# LCDwen.net
KiCad netlist of a schematic drawn in Altium Designer
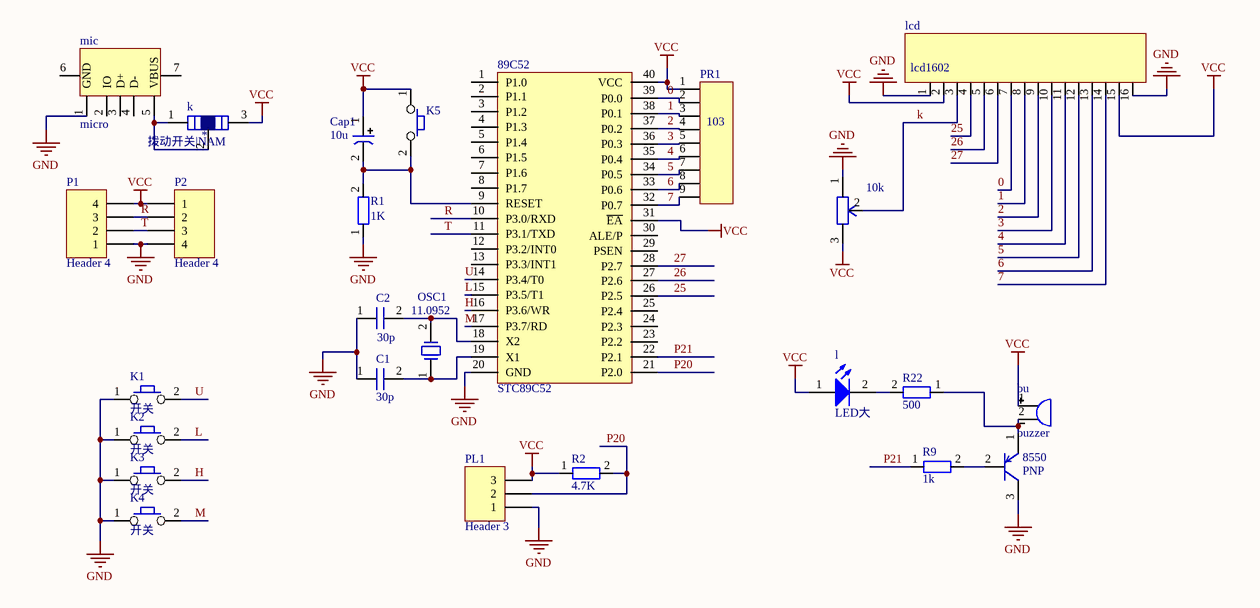
[diagram p0: LCDwen.SchDoc]

(export (version "E")
  (design (tool "Eeschema 10.0.6"))
  (components
    (comp (ref "10k") (value "~") (footprint "蓝白电位器") (libsource (lib "1412220207梁新坚元器件库") (part "蓝白电位器")))
    (comp (ref "89C52")
      (value "STC89C52")
      (footprint "AT89C52")
      (libsource (lib "1412220207梁新坚元器件库") (part "STC89C52"))
    )
    (comp (ref "8550") (value "PNP") (footprint "三极管PNP") (libsource (lib "1412220207梁新坚元器件库") (part "PNP")))
    (comp (ref "bu")
      (value "buzzer")
      (footprint "buzzer")
      (libsource (lib "1412220207梁新坚元器件库") (part "buzzer"))
    )
    (comp (ref "C1") (value "30p") (footprint "电容。") (libsource (lib "1412220207梁新坚元器件库") (part "电容")))
    (comp (ref "C2") (value "30p") (footprint "电容。") (libsource (lib "1412220207梁新坚元器件库") (part "电容")))
    (comp (ref "Cap1") (value "10u") (footprint "电容") (libsource (lib "1412220207梁新坚元器件库") (part "电解电容")))
    (comp (ref "k")
      (value "*")
      (footprint "拨动开关")
      (fields (field (name "ALTIUM_UNNAMED_1") "拨动开关"))
      (libsource (lib "1412220207梁新坚元器件库") (part "拨动开关"))
    )
    (comp (ref "K1")
      (value "~")
      (footprint "开关")
      (fields (field (name "COMMEN") "开关"))
      (libsource (lib "1412220207梁新坚元器件库") (part "开关"))
    )
    (comp (ref "K2")
      (value "~")
      (footprint "开关")
      (fields (field (name "COMMEN") "开关"))
      (libsource (lib "1412220207梁新坚元器件库") (part "开关"))
    )
    (comp (ref "K3")
      (value "~")
      (footprint "开关")
      (fields (field (name "COMMEN") "开关"))
      (libsource (lib "1412220207梁新坚元器件库") (part "开关"))
    )
    (comp (ref "K4")
      (value "~")
      (footprint "开关")
      (fields (field (name "COMMEN") "开关"))
      (libsource (lib "1412220207梁新坚元器件库") (part "开关"))
    )
    (comp (ref "K5") (value "~") (footprint "开关") (libsource (lib "1412220207梁新坚元器件库") (part "开关")))
    (comp (ref "l") (value "LED大") (footprint "LED大") (libsource (lib "1412220207梁新坚元器件库") (part "LED大")))
    (comp (ref "lcd")
      (value "lcd1602")
      (footprint "lcd1602")
      (libsource (lib "1412220207梁新坚元器件库") (part "lcd1602"))
    )
    (comp (ref "mic")
      (value "micro")
      (footprint "MICRO")
      (libsource (lib "1412220207梁新坚元器件库") (part "micro"))
    )
    (comp (ref "OSC1") (value "11.0952") (footprint "晶震") (libsource (lib "1412220207梁新坚元器件库") (part "晶震")))
    (comp (ref "P1")
      (value "Header 4")
      (footprint "HDR1X4")
      (description "Header, 4-Pin")
      (fields (field (name "PUBLISHER") "Altium Limited"))
      (libsource (lib "Miscellaneous Connectors") (part "Header 4"))
    )
    (comp (ref "P2")
      (value "Header 4")
      (footprint "HDR1X4")
      (description "Header, 4-Pin")
      (fields (field (name "PUBLISHER") "Altium Limited"))
      (libsource (lib "") (part "Header 4_1"))
    )
    (comp (ref "PL1")
      (value "Header 3")
      (footprint "HDR1X3")
      (description "Header, 3-Pin")
      (fields (field (name "PUBLISHER") "Altium Limited"))
      (libsource (lib "Miscellaneous Connectors") (part "Header 3"))
    )
    (comp (ref "PR1") (value "103") (footprint "排阻") (libsource (lib "1412220207梁新坚元器件库") (part "排阻")))
    (comp (ref "R1") (value "1K") (footprint "电阻") (libsource (lib "1412220207梁新坚元器件库") (part "电阻")))
    (comp (ref "R2") (value "4.7K") (footprint "电阻") (libsource (lib "1412220207梁新坚元器件库") (part "电阻")))
    (comp (ref "R9") (value "1k") (footprint "电阻") (libsource (lib "1412220207梁新坚元器件库") (part "电阻")))
    (comp (ref "R22") (value "500") (footprint "电阻") (libsource (lib "1412220207梁新坚元器件库") (part "电阻")))
  )
  (nets
    (net (code "1") (name "/0") (class "Default")
      (node (ref "89C52") (pin "39") (pinfunction "P0.0_39") (pintype "passive"))
      (node (ref "PR1") (pin "2") (pinfunction "2_2") (pintype "passive"))
      (node (ref "lcd") (pin "7") (pinfunction "7_7") (pintype "passive"))
    )
    (net (code "2") (name "/1") (class "Default")
      (node (ref "89C52") (pin "38") (pinfunction "P0.1_38") (pintype "passive"))
      (node (ref "PR1") (pin "3") (pinfunction "3_3") (pintype "passive"))
      (node (ref "lcd") (pin "8") (pinfunction "8_8") (pintype "passive"))
    )
    (net (code "3") (name "/2") (class "Default")
      (node (ref "89C52") (pin "37") (pinfunction "P0.2_37") (pintype "passive"))
      (node (ref "PR1") (pin "4") (pinfunction "4_4") (pintype "passive"))
      (node (ref "lcd") (pin "9") (pinfunction "9_9") (pintype "passive"))
    )
    (net (code "4") (name "/3") (class "Default")
      (node (ref "89C52") (pin "36") (pinfunction "P0.3_36") (pintype "passive"))
      (node (ref "PR1") (pin "5") (pinfunction "5_5") (pintype "passive"))
      (node (ref "lcd") (pin "10") (pinfunction "10_10") (pintype "passive"))
    )
    (net (code "5") (name "/4") (class "Default")
      (node (ref "89C52") (pin "35") (pinfunction "P0.4_35") (pintype "passive"))
      (node (ref "PR1") (pin "6") (pinfunction "6_6") (pintype "passive"))
      (node (ref "lcd") (pin "11") (pinfunction "11_11") (pintype "passive"))
    )
    (net (code "6") (name "/5") (class "Default")
      (node (ref "89C52") (pin "34") (pinfunction "P0.5_34") (pintype "passive"))
      (node (ref "PR1") (pin "7") (pinfunction "7_7") (pintype "passive"))
      (node (ref "lcd") (pin "12") (pinfunction "12_12") (pintype "passive"))
    )
    (net (code "7") (name "/6") (class "Default")
      (node (ref "89C52") (pin "33") (pinfunction "P0.6_33") (pintype "passive"))
      (node (ref "PR1") (pin "8") (pinfunction "8_8") (pintype "passive"))
      (node (ref "lcd") (pin "13") (pinfunction "13_13") (pintype "passive"))
    )
    (net (code "8") (name "/7") (class "Default")
      (node (ref "89C52") (pin "32") (pinfunction "P0.7_32") (pintype "passive"))
      (node (ref "PR1") (pin "9") (pinfunction "9_9") (pintype "passive"))
      (node (ref "lcd") (pin "14") (pinfunction "14_14") (pintype "passive"))
    )
    (net (code "9") (name "/25") (class "Default")
      (node (ref "89C52") (pin "26") (pinfunction "P2.5_26") (pintype "passive"))
      (node (ref "lcd") (pin "4") (pinfunction "4_4") (pintype "passive"))
    )
    (net (code "10") (name "/26") (class "Default")
      (node (ref "89C52") (pin "27") (pinfunction "P2.6_27") (pintype "passive"))
      (node (ref "lcd") (pin "5") (pinfunction "5_5") (pintype "passive"))
    )
    (net (code "11") (name "/27") (class "Default")
      (node (ref "89C52") (pin "28") (pinfunction "P2.7_28") (pintype "passive"))
      (node (ref "lcd") (pin "6") (pinfunction "6_6") (pintype "passive"))
    )
    (net (code "12") (name "/H") (class "Default")
      (node (ref "89C52") (pin "16") (pinfunction "P3.6/WR_16") (pintype "passive"))
      (node (ref "K3") (pin "2") (pinfunction "2_2") (pintype "passive"))
    )
    (net (code "13") (name "/L") (class "Default")
      (node (ref "89C52") (pin "15") (pinfunction "P3.5/T1_15") (pintype "passive"))
      (node (ref "K2") (pin "2") (pinfunction "2_2") (pintype "passive"))
    )
    (net (code "14") (name "/M") (class "Default")
      (node (ref "89C52") (pin "17") (pinfunction "P3.7/RD_17") (pintype "passive"))
      (node (ref "K4") (pin "2") (pinfunction "2_2") (pintype "passive"))
    )
    (net (code "15") (name "/P20") (class "Default")
      (node (ref "89C52") (pin "21") (pinfunction "P2.0_21") (pintype "passive"))
      (node (ref "PL1") (pin "2") (pinfunction "2_2") (pintype "passive"))
      (node (ref "R2") (pin "2") (pinfunction "2_2") (pintype "passive"))
    )
    (net (code "16") (name "/P21") (class "Default")
      (node (ref "89C52") (pin "22") (pinfunction "P2.1_22") (pintype "passive"))
      (node (ref "R9") (pin "1") (pinfunction "1_1") (pintype "passive"))
    )
    (net (code "17") (name "/R") (class "Default")
      (node (ref "89C52") (pin "10") (pinfunction "P3.0/RXD_10") (pintype "passive"))
      (node (ref "P1") (pin "3") (pinfunction "3_3") (pintype "passive"))
      (node (ref "P2") (pin "2") (pinfunction "2_2") (pintype "passive"))
    )
    (net (code "18") (name "/T") (class "Default")
      (node (ref "89C52") (pin "11") (pinfunction "P3.1/TXD_11") (pintype "passive"))
      (node (ref "P1") (pin "2") (pinfunction "2_2") (pintype "passive"))
      (node (ref "P2") (pin "3") (pinfunction "3_3") (pintype "passive"))
    )
    (net (code "19") (name "/U") (class "Default")
      (node (ref "89C52") (pin "14") (pinfunction "P3.4/T0_14") (pintype "passive"))
      (node (ref "K1") (pin "2") (pinfunction "2_2") (pintype "passive"))
    )
    (net (code "20") (name "/k") (class "Default")
      (node (ref "10k") (pin "2") (pinfunction "2_2") (pintype "passive"))
      (node (ref "lcd") (pin "3") (pinfunction "3_3") (pintype "passive"))
    )
    (net (code "21") (name "GND") (class "Default")
      (node (ref "10k") (pin "1") (pinfunction "1_1") (pintype "passive"))
      (node (ref "8550") (pin "3") (pinfunction "3_3") (pintype "passive"))
      (node (ref "89C52") (pin "20") (pinfunction "GND_20") (pintype "passive"))
      (node (ref "C1") (pin "1") (pinfunction "1_1") (pintype "passive"))
      (node (ref "C2") (pin "1") (pinfunction "1_1") (pintype "passive"))
      (node (ref "K1") (pin "1") (pinfunction "1_1") (pintype "passive"))
      (node (ref "K2") (pin "1") (pinfunction "1_1") (pintype "passive"))
      (node (ref "K3") (pin "1") (pinfunction "1_1") (pintype "passive"))
      (node (ref "K4") (pin "1") (pinfunction "1_1") (pintype "passive"))
      (node (ref "P1") (pin "1") (pinfunction "1_1") (pintype "passive"))
      (node (ref "P2") (pin "4") (pinfunction "4_4") (pintype "passive"))
      (node (ref "PL1") (pin "1") (pinfunction "1_1") (pintype "passive"))
      (node (ref "R1") (pin "1") (pinfunction "1_1") (pintype "passive"))
      (node (ref "lcd") (pin "1") (pinfunction "1_1") (pintype "passive"))
      (node (ref "lcd") (pin "16") (pinfunction "16_16") (pintype "passive"))
      (node (ref "mic") (pin "1") (pinfunction "GND_1") (pintype "passive"))
    )
    (net (code "22") (name "Net-(89C52-RESET)") (class "Default")
      (node (ref "89C52") (pin "9") (pinfunction "RESET_9") (pintype "passive"))
      (node (ref "Cap1") (pin "2") (pinfunction "2_2") (pintype "passive"))
      (node (ref "K5") (pin "2") (pinfunction "2_2") (pintype "passive"))
      (node (ref "R1") (pin "2") (pinfunction "2_2") (pintype "passive"))
    )
    (net (code "23") (name "Net-(89C52-X1)") (class "Default")
      (node (ref "89C52") (pin "19") (pinfunction "X1_19") (pintype "passive"))
      (node (ref "C1") (pin "2") (pinfunction "2_2") (pintype "passive"))
      (node (ref "OSC1") (pin "1") (pinfunction "1_1") (pintype "passive"))
    )
    (net (code "24") (name "Net-(89C52-X2)") (class "Default")
      (node (ref "89C52") (pin "18") (pinfunction "X2_18") (pintype "passive"))
      (node (ref "C2") (pin "2") (pinfunction "2_2") (pintype "passive"))
      (node (ref "OSC1") (pin "2") (pinfunction "2_2") (pintype "passive"))
    )
    (net (code "25") (name "Net-(8550-Pad1)") (class "Default")
      (node (ref "8550") (pin "1") (pinfunction "1_1") (pintype "passive"))
      (node (ref "R22") (pin "1") (pinfunction "1_1") (pintype "passive"))
      (node (ref "bu") (pin "2") (pinfunction "2_2") (pintype "passive"))
    )
    (net (code "26") (name "Net-(8550-Pad2)") (class "Default")
      (node (ref "8550") (pin "2") (pinfunction "2_2") (pintype "passive"))
      (node (ref "R9") (pin "2") (pinfunction "2_2") (pintype "passive"))
    )
    (net (code "27") (name "Net-(R22-Pad2)") (class "Default")
      (node (ref "R22") (pin "2") (pinfunction "2_2") (pintype "passive"))
      (node (ref "l") (pin "2") (pinfunction "2_2") (pintype "passive"))
    )
    (net (code "28") (name "Net-(mic-VBUS)") (class "Default")
      (node (ref "k") (pin "1") (pinfunction "1_1") (pintype "passive"))
      (node (ref "k") (pin "2") (pinfunction "2_2") (pintype "passive"))
      (node (ref "mic") (pin "5") (pinfunction "VBUS_5") (pintype "passive"))
    )
    (net (code "29") (name "VCC") (class "Default")
      (node (ref "10k") (pin "3") (pinfunction "3_3") (pintype "passive"))
      (node (ref "89C52") (pin "31") (pinfunction "~{EA}_31") (pintype "passive"))
      (node (ref "89C52") (pin "40") (pinfunction "VCC_40") (pintype "passive"))
      (node (ref "Cap1") (pin "1") (pinfunction "1_1") (pintype "passive"))
      (node (ref "K5") (pin "1") (pinfunction "1_1") (pintype "passive"))
      (node (ref "P1") (pin "4") (pinfunction "4_4") (pintype "passive"))
      (node (ref "P2") (pin "1") (pinfunction "1_1") (pintype "passive"))
      (node (ref "PL1") (pin "3") (pinfunction "3_3") (pintype "passive"))
      (node (ref "PR1") (pin "1") (pinfunction "1_1") (pintype "passive"))
      (node (ref "R2") (pin "1") (pinfunction "1_1") (pintype "passive"))
      (node (ref "bu") (pin "1") (pinfunction "1_1") (pintype "passive"))
      (node (ref "k") (pin "3") (pinfunction "3_3") (pintype "passive"))
      (node (ref "l") (pin "1") (pinfunction "1_1") (pintype "passive"))
      (node (ref "lcd") (pin "15") (pinfunction "15_15") (pintype "passive"))
      (node (ref "lcd") (pin "2") (pinfunction "2_2") (pintype "passive"))
    )
    (net (code "30") (name "unconnected-(89C52-ALE{slash}P-Pad30)") (class "Default")
      (node (ref "89C52") (pin "30") (pinfunction "ALE/P_30") (pintype "passive"))
    )
    (net (code "31") (name "unconnected-(89C52-P1.0-Pad1)") (class "Default")
      (node (ref "89C52") (pin "1") (pinfunction "P1.0_1") (pintype "passive"))
    )
    (net (code "32") (name "unconnected-(89C52-P1.1-Pad2)") (class "Default")
      (node (ref "89C52") (pin "2") (pinfunction "P1.1_2") (pintype "passive"))
    )
    (net (code "33") (name "unconnected-(89C52-P1.2-Pad3)") (class "Default")
      (node (ref "89C52") (pin "3") (pinfunction "P1.2_3") (pintype "passive"))
    )
    (net (code "34") (name "unconnected-(89C52-P1.3-Pad4)") (class "Default")
      (node (ref "89C52") (pin "4") (pinfunction "P1.3_4") (pintype "passive"))
    )
    (net (code "35") (name "unconnected-(89C52-P1.4-Pad5)") (class "Default")
      (node (ref "89C52") (pin "5") (pinfunction "P1.4_5") (pintype "passive"))
    )
    (net (code "36") (name "unconnected-(89C52-P1.5-Pad6)") (class "Default")
      (node (ref "89C52") (pin "6") (pinfunction "P1.5_6") (pintype "passive"))
    )
    (net (code "37") (name "unconnected-(89C52-P1.6-Pad7)") (class "Default")
      (node (ref "89C52") (pin "7") (pinfunction "P1.6_7") (pintype "passive"))
    )
    (net (code "38") (name "unconnected-(89C52-P1.7-Pad8)") (class "Default")
      (node (ref "89C52") (pin "8") (pinfunction "P1.7_8") (pintype "passive"))
    )
    (net (code "39") (name "unconnected-(89C52-P2.2-Pad23)") (class "Default")
      (node (ref "89C52") (pin "23") (pinfunction "P2.2_23") (pintype "passive"))
    )
    (net (code "40") (name "unconnected-(89C52-P2.3-Pad24)") (class "Default")
      (node (ref "89C52") (pin "24") (pinfunction "P2.3_24") (pintype "passive"))
    )
    (net (code "41") (name "unconnected-(89C52-P2.4-Pad25)") (class "Default")
      (node (ref "89C52") (pin "25") (pinfunction "P2.4_25") (pintype "passive"))
    )
    (net (code "42") (name "unconnected-(89C52-P3.2{slash}INT0-Pad12)") (class "Default")
      (node (ref "89C52") (pin "12") (pinfunction "P3.2/INT0_12") (pintype "passive"))
    )
    (net (code "43") (name "unconnected-(89C52-P3.3{slash}INT1-Pad13)") (class "Default")
      (node (ref "89C52") (pin "13") (pinfunction "P3.3/INT1_13") (pintype "passive"))
    )
    (net (code "44") (name "unconnected-(89C52-PSEN-Pad29)") (class "Default")
      (node (ref "89C52") (pin "29") (pinfunction "PSEN_29") (pintype "passive"))
    )
    (net (code "45") (name "unconnected-(mic-D+-Pad3)") (class "Default")
      (node (ref "mic") (pin "3") (pinfunction "D+_3") (pintype "passive"))
    )
    (net (code "46") (name "unconnected-(mic-D--Pad4)") (class "Default")
      (node (ref "mic") (pin "4") (pinfunction "D-_4") (pintype "passive"))
    )
    (net (code "47") (name "unconnected-(mic-IO-Pad2)") (class "Default")
      (node (ref "mic") (pin "2") (pinfunction "IO_2") (pintype "passive"))
    )
    (net (code "48") (name "unconnected-(mic-Pad6)") (class "Default")
      (node (ref "mic") (pin "6") (pinfunction "6_6") (pintype "passive"))
    )
    (net (code "49") (name "unconnected-(mic-Pad7)") (class "Default")
      (node (ref "mic") (pin "7") (pinfunction "7_7") (pintype "passive"))
    )
  )
)
